# igonzocam_motionsensor.net
KiCad netlist of a schematic drawn in EAGLE
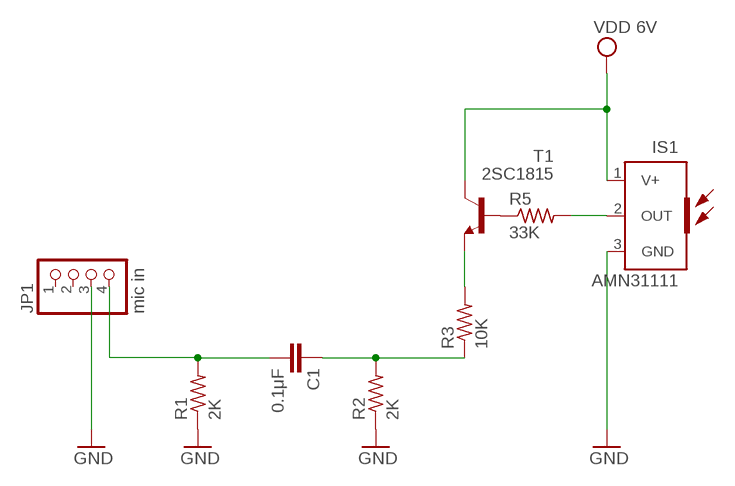
[diagram p0: schematic, sheet 1]

(export (version "E")
  (design (tool "Eeschema 10.0.6"))
  (components
    (comp (ref "C1")
      (value "0.1μF")
      (footprint "eagle-import:C5B3")
      (libsource (lib "eagle-import") (part "C5/3"))
    )
    (comp (ref "IS1")
      (value "AMN31111")
      (footprint "eagle-import:TO39")
      (libsource (lib "eagle-import") (part "LME-346-F"))
    )
    (comp (ref "JP1")
      (value "mic in")
      (footprint "eagle-import:1X04")
      (libsource (lib "eagle-import") (part "PINHD-1X4"))
    )
    (comp (ref "R1")
      (value "2K")
      (footprint "eagle-import:0204_7")
      (libsource (lib "eagle-import") (part "R-US_0204/7"))
    )
    (comp (ref "R2")
      (value "2K")
      (footprint "eagle-import:0204_7")
      (libsource (lib "eagle-import") (part "R-US_0204/7"))
    )
    (comp (ref "R3")
      (value "10K")
      (footprint "eagle-import:0204_7")
      (libsource (lib "eagle-import") (part "R-US_0204/7"))
    )
    (comp (ref "R5")
      (value "33K")
      (footprint "eagle-import:0204_7")
      (libsource (lib "eagle-import") (part "R-US_0204/7"))
    )
    (comp (ref "T1")
      (value "2SC1815")
      (footprint "eagle-import:TO92-ECB")
      (libsource (lib "eagle-import") (part "2SC1815"))
    )
  )
  (nets
    (net (code "1") (name "GND") (class "Default")
      (node (ref "IS1") (pin "3") (pinfunction "GND_3") (pintype "power_in"))
      (node (ref "JP1") (pin "3") (pinfunction "3_3") (pintype "passive"))
      (node (ref "R1") (pin "1") (pinfunction "1_1") (pintype "passive"))
      (node (ref "R2") (pin "1") (pinfunction "1_1") (pintype "passive"))
    )
    (net (code "2") (name "Net-(C1-Pad1)") (class "Default")
      (node (ref "C1") (pin "1") (pinfunction "1_1") (pintype "passive"))
      (node (ref "R2") (pin "2") (pinfunction "2_2") (pintype "passive"))
      (node (ref "R3") (pin "1") (pinfunction "1_1") (pintype "passive"))
    )
    (net (code "3") (name "Net-(C1-Pad2)") (class "Default")
      (node (ref "C1") (pin "2") (pinfunction "2_2") (pintype "passive"))
      (node (ref "JP1") (pin "4") (pinfunction "4_4") (pintype "passive"))
      (node (ref "R1") (pin "2") (pinfunction "2_2") (pintype "passive"))
    )
    (net (code "4") (name "Net-(IS1-OUT)") (class "Default")
      (node (ref "IS1") (pin "2") (pinfunction "OUT_2") (pintype "output"))
      (node (ref "R5") (pin "2") (pinfunction "2_2") (pintype "passive"))
    )
    (net (code "5") (name "Net-(R3-Pad2)") (class "Default")
      (node (ref "R3") (pin "2") (pinfunction "2_2") (pintype "passive"))
      (node (ref "T1") (pin "E") (pinfunction "E_E") (pintype "passive"))
    )
    (net (code "6") (name "Net-(R5-Pad1)") (class "Default")
      (node (ref "R5") (pin "1") (pinfunction "1_1") (pintype "passive"))
      (node (ref "T1") (pin "B") (pinfunction "B_B") (pintype "passive"))
    )
    (net (code "7") (name "VDD 6V") (class "Default")
      (node (ref "IS1") (pin "1") (pinfunction "V+_1") (pintype "power_in"))
      (node (ref "T1") (pin "C") (pinfunction "C_C") (pintype "passive"))
    )
    (net (code "8") (name "unconnected-(JP1-Pad1)") (class "Default")
      (node (ref "JP1") (pin "1") (pinfunction "1_1") (pintype "passive"))
    )
    (net (code "9") (name "unconnected-(JP1-Pad2)") (class "Default")
      (node (ref "JP1") (pin "2") (pinfunction "2_2") (pintype "passive"))
    )
  )
)
